# oscillVRL75.net
KiCad netlist of a schematic drawn in EAGLE
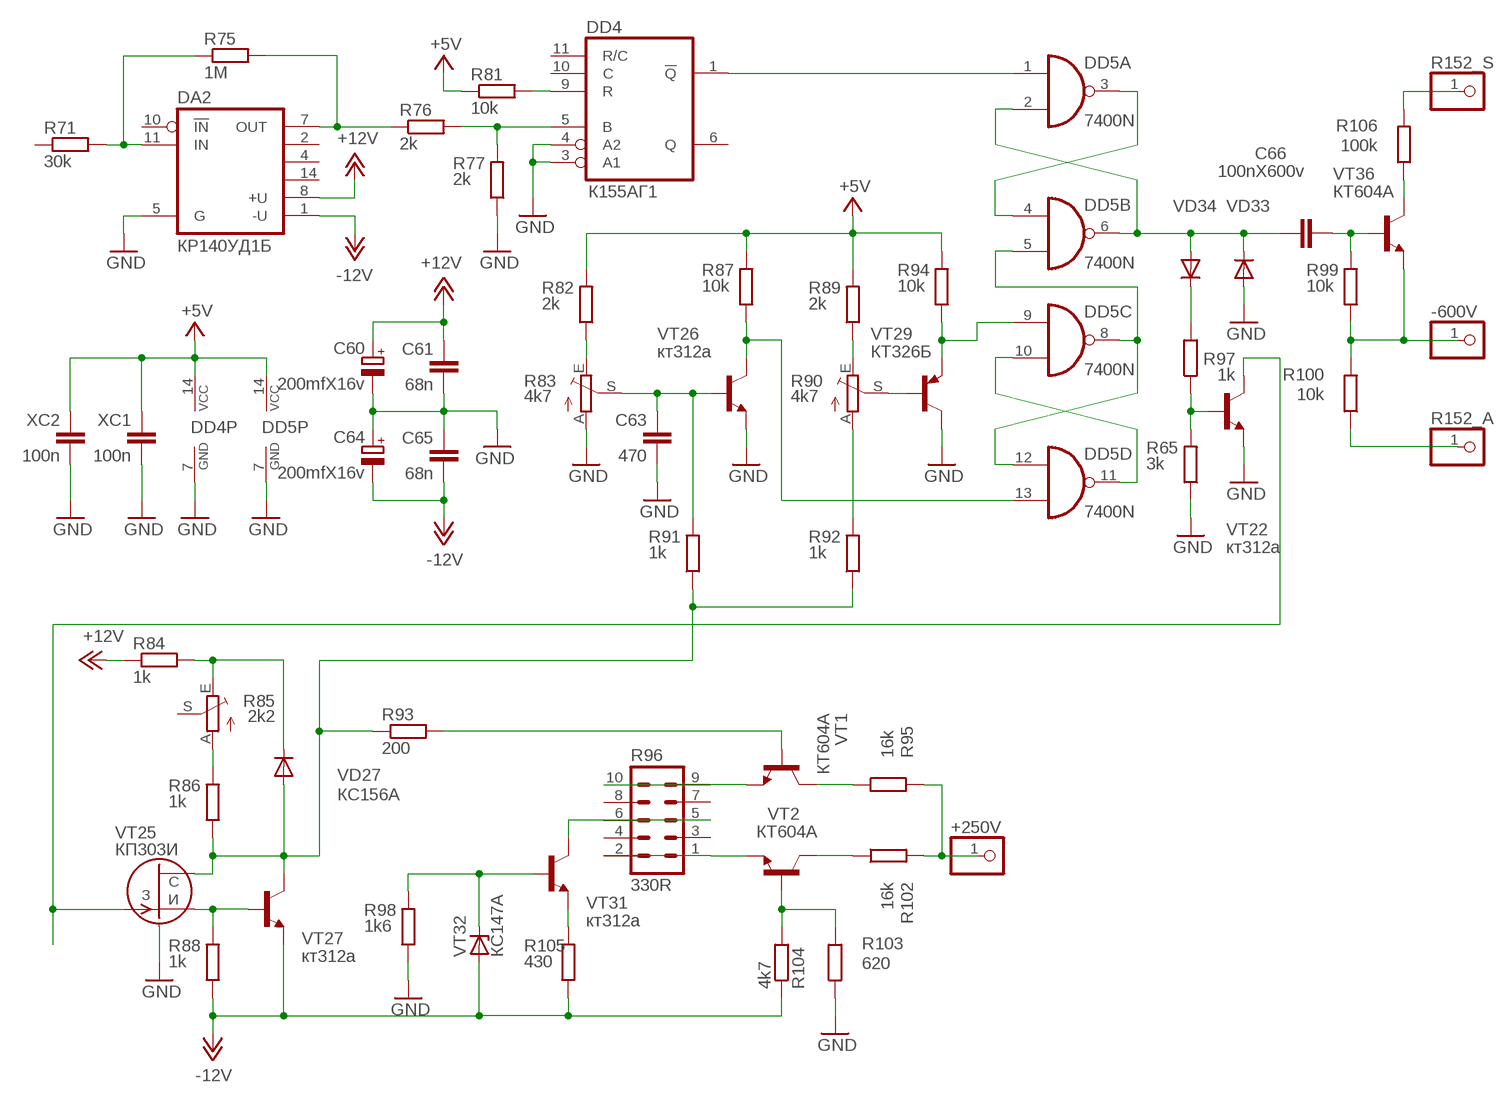
[diagram p0: schematic, sheet 1]

(export (version "E")
  (design (tool "Eeschema 10.0.6"))
  (components
    (comp (ref "+250V")
      (value "PINHD-1X1")
      (footprint "eagle-import:1X01")
      (libsource (lib "eagle-import") (part "PINHD-1X1"))
    )
    (comp (ref "-600V")
      (value "PINHD-1X1")
      (footprint "eagle-import:1X01")
      (libsource (lib "eagle-import") (part "PINHD-1X1"))
    )
    (comp (ref "C60")
      (value "200mfX16v")
      (footprint "eagle-import:E2,5-6")
      (libsource (lib "eagle-import") (part "CPOL-EUE2.5-6"))
    )
    (comp (ref "C61")
      (value "68n")
      (footprint "eagle-import:C0805")
      (libsource (lib "eagle-import") (part "C-EUC0805"))
    )
    (comp (ref "C63")
      (value "470")
      (footprint "eagle-import:C025-025X050")
      (libsource (lib "eagle-import") (part "C-EU025-025X050"))
    )
    (comp (ref "C64")
      (value "200mfX16v")
      (footprint "eagle-import:E2,5-6")
      (libsource (lib "eagle-import") (part "CPOL-EUE2.5-6"))
    )
    (comp (ref "C65")
      (value "68n")
      (footprint "eagle-import:C0805")
      (libsource (lib "eagle-import") (part "C-EUC0805"))
    )
    (comp (ref "C66")
      (value "100nX600v")
      (footprint "eagle-import:C050-025X075")
      (libsource (lib "eagle-import") (part "C-EU050-025X075"))
    )
    (comp (ref "DA2")
      (value "КР140УД1Б")
      (footprint "eagle-import:DIL14")
      (libsource (lib "eagle-import") (part "140UD1(KR)"))
    )
    (comp (ref "DD4")
      (value "К155АГ1")
      (footprint "eagle-import:DIL14")
      (libsource (lib "eagle-import") (part "74121N"))
    )
    (comp (ref "DD5")
      (value "7400N")
      (footprint "eagle-import:DIL14")
      (libsource (lib "eagle-import") (part "7400N"))
    )
    (comp (ref "R65")
      (value "3k")
      (footprint "eagle-import:M0805")
      (libsource (lib "eagle-import") (part "R-EU_M0805"))
    )
    (comp (ref "R71")
      (value "30k")
      (footprint "eagle-import:M0805")
      (libsource (lib "eagle-import") (part "R-EU_M0805"))
    )
    (comp (ref "R75")
      (value "1M")
      (footprint "eagle-import:M0805")
      (libsource (lib "eagle-import") (part "R-EU_M0805"))
    )
    (comp (ref "R76")
      (value "2k")
      (footprint "eagle-import:M0805")
      (libsource (lib "eagle-import") (part "R-EU_M0805"))
    )
    (comp (ref "R77")
      (value "2k")
      (footprint "eagle-import:M0805")
      (libsource (lib "eagle-import") (part "R-EU_M0805"))
    )
    (comp (ref "R81")
      (value "10k")
      (footprint "eagle-import:M0805")
      (libsource (lib "eagle-import") (part "R-EU_M0805"))
    )
    (comp (ref "R82")
      (value "2k")
      (footprint "eagle-import:M0805")
      (libsource (lib "eagle-import") (part "R-EU_M0805"))
    )
    (comp (ref "R83")
      (value "4k7")
      (footprint "eagle-import:S64Y")
      (libsource (lib "eagle-import") (part "TRIM_EU-S64Y"))
    )
    (comp (ref "R84")
      (value "1k")
      (footprint "eagle-import:M0805")
      (libsource (lib "eagle-import") (part "R-EU_M0805"))
    )
    (comp (ref "R85")
      (value "2k2")
      (footprint "eagle-import:S64Y")
      (libsource (lib "eagle-import") (part "TRIM_EU-S64Y"))
    )
    (comp (ref "R86")
      (value "1k")
      (footprint "eagle-import:M0805")
      (libsource (lib "eagle-import") (part "R-EU_M0805"))
    )
    (comp (ref "R87")
      (value "10k")
      (footprint "eagle-import:M0805")
      (libsource (lib "eagle-import") (part "R-EU_M0805"))
    )
    (comp (ref "R88")
      (value "1k")
      (footprint "eagle-import:M0805")
      (libsource (lib "eagle-import") (part "R-EU_M0805"))
    )
    (comp (ref "R89")
      (value "2k")
      (footprint "eagle-import:M0805")
      (libsource (lib "eagle-import") (part "R-EU_M0805"))
    )
    (comp (ref "R90")
      (value "4k7")
      (footprint "eagle-import:S64Y")
      (libsource (lib "eagle-import") (part "TRIM_EU-S64Y"))
    )
    (comp (ref "R91")
      (value "1k")
      (footprint "eagle-import:M0805")
      (libsource (lib "eagle-import") (part "R-EU_M0805"))
    )
    (comp (ref "R92")
      (value "1k")
      (footprint "eagle-import:M0805")
      (libsource (lib "eagle-import") (part "R-EU_M0805"))
    )
    (comp (ref "R93")
      (value "200")
      (footprint "eagle-import:M0805")
      (libsource (lib "eagle-import") (part "R-EU_M0805"))
    )
    (comp (ref "R94")
      (value "10k")
      (footprint "eagle-import:M0805")
      (libsource (lib "eagle-import") (part "R-EU_M0805"))
    )
    (comp (ref "R95")
      (value "16k")
      (footprint "eagle-import:M1206")
      (libsource (lib "eagle-import") (part "R-EU_M1206"))
    )
    (comp (ref "R96")
      (value "330R")
      (footprint "eagle-import:MA05-2")
      (libsource (lib "eagle-import") (part "MA05-2"))
    )
    (comp (ref "R97")
      (value "1k")
      (footprint "eagle-import:M0805")
      (libsource (lib "eagle-import") (part "R-EU_M0805"))
    )
    (comp (ref "R98")
      (value "1k6")
      (footprint "eagle-import:M0805")
      (libsource (lib "eagle-import") (part "R-EU_M0805"))
    )
    (comp (ref "R99")
      (value "10k")
      (footprint "eagle-import:M1206")
      (libsource (lib "eagle-import") (part "R-EU_M1206"))
    )
    (comp (ref "R100")
      (value "10k")
      (footprint "eagle-import:M1206")
      (libsource (lib "eagle-import") (part "R-EU_M1206"))
    )
    (comp (ref "R102")
      (value "16k")
      (footprint "eagle-import:M1206")
      (libsource (lib "eagle-import") (part "R-EU_M1206"))
    )
    (comp (ref "R103")
      (value "620")
      (footprint "eagle-import:M1206")
      (libsource (lib "eagle-import") (part "R-EU_M1206"))
    )
    (comp (ref "R104")
      (value "4k7")
      (footprint "eagle-import:M1206")
      (libsource (lib "eagle-import") (part "R-EU_M1206"))
    )
    (comp (ref "R105")
      (value "430")
      (footprint "eagle-import:M0805")
      (libsource (lib "eagle-import") (part "R-EU_M0805"))
    )
    (comp (ref "R106")
      (value "100k")
      (footprint "eagle-import:M1206")
      (libsource (lib "eagle-import") (part "R-EU_M1206"))
    )
    (comp (ref "R152_A")
      (value "PINHD-1X1")
      (footprint "eagle-import:1X01")
      (libsource (lib "eagle-import") (part "PINHD-1X1"))
    )
    (comp (ref "R152_S")
      (value "PINHD-1X1")
      (footprint "eagle-import:1X01")
      (libsource (lib "eagle-import") (part "PINHD-1X1"))
    )
    (comp (ref "VD27")
      (value "КС156А")
      (footprint "eagle-import:SOD80C")
      (libsource (lib "eagle-import") (part "DIODE-SOD80C"))
    )
    (comp (ref "VD33")
      (value "DIODE-SOD80C")
      (footprint "eagle-import:SOD80C")
      (libsource (lib "eagle-import") (part "DIODE-SOD80C"))
    )
    (comp (ref "VD34")
      (value "DIODE-SOD80C")
      (footprint "eagle-import:SOD80C")
      (libsource (lib "eagle-import") (part "DIODE-SOD80C"))
    )
    (comp (ref "VT1")
      (value "КТ604А")
      (footprint "eagle-import:TO126V")
      (libsource (lib "eagle-import") (part "-NPN-TO126V"))
    )
    (comp (ref "VT2")
      (value "КТ604А")
      (footprint "eagle-import:TO126V")
      (libsource (lib "eagle-import") (part "-NPN-TO126V"))
    )
    (comp (ref "VT22")
      (value "кт312а")
      (footprint "eagle-import:TO92-ECB")
      (libsource (lib "eagle-import") (part "-NPN-TO92-ECB"))
    )
    (comp (ref "VT25")
      (value "КП303И")
      (footprint "eagle-import:TO72")
      (libsource (lib "eagle-import") (part "КП303И"))
    )
    (comp (ref "VT26")
      (value "кт312а")
      (footprint "eagle-import:TO92-ECB")
      (libsource (lib "eagle-import") (part "-NPN-TO92-ECB"))
    )
    (comp (ref "VT27")
      (value "кт312а")
      (footprint "eagle-import:TO92-ECB")
      (libsource (lib "eagle-import") (part "-NPN-TO92-ECB"))
    )
    (comp (ref "VT29")
      (value "КТ326Б")
      (footprint "eagle-import:TO18")
      (libsource (lib "eagle-import") (part "-PNP-TO18-EBC2N3963"))
    )
    (comp (ref "VT31")
      (value "кт312а")
      (footprint "eagle-import:TO92-ECB")
      (libsource (lib "eagle-import") (part "-NPN-TO92-ECB"))
    )
    (comp (ref "VT32")
      (value "КС147А")
      (footprint "eagle-import:DO35Z10")
      (libsource (lib "eagle-import") (part "ZENER-DIODEDO35Z10"))
    )
    (comp (ref "VT36")
      (value "КТ604А")
      (footprint "eagle-import:TO126V")
      (libsource (lib "eagle-import") (part "-NPN-TO126V"))
    )
    (comp (ref "XC1")
      (value "100n")
      (footprint "eagle-import:C0805")
      (libsource (lib "eagle-import") (part "C-EUC0805"))
    )
    (comp (ref "XC2")
      (value "100n")
      (footprint "eagle-import:C0805")
      (libsource (lib "eagle-import") (part "C-EUC0805"))
    )
  )
  (nets
    (net (code "1") (name "+5V") (class "Default")
      (node (ref "DD4") (pin "14") (pinfunction "VCC_14") (pintype "power_in"))
      (node (ref "DD5") (pin "14") (pinfunction "VCC_14") (pintype "power_in"))
      (node (ref "R81") (pin "1") (pinfunction "1_1") (pintype "passive"))
      (node (ref "R82") (pin "2") (pinfunction "2_2") (pintype "passive"))
      (node (ref "R87") (pin "2") (pinfunction "2_2") (pintype "passive"))
      (node (ref "R89") (pin "2") (pinfunction "2_2") (pintype "passive"))
      (node (ref "R94") (pin "2") (pinfunction "2_2") (pintype "passive"))
      (node (ref "XC1") (pin "1") (pinfunction "1_1") (pintype "passive"))
      (node (ref "XC2") (pin "1") (pinfunction "1_1") (pintype "passive"))
    )
    (net (code "2") (name "+12V") (class "Default")
      (node (ref "C60") (pin "+") (pinfunction "+_+") (pintype "passive"))
      (node (ref "C61") (pin "1") (pinfunction "1_1") (pintype "passive"))
      (node (ref "DA2") (pin "8") (pinfunction "+U_8") (pintype "input"))
      (node (ref "R84") (pin "1") (pinfunction "1_1") (pintype "passive"))
    )
    (net (code "3") (name "-12V") (class "Default")
      (node (ref "C64") (pin "-") (pinfunction "-_-") (pintype "passive"))
      (node (ref "C65") (pin "2") (pinfunction "2_2") (pintype "passive"))
      (node (ref "DA2") (pin "1") (pinfunction "-U_1") (pintype "input"))
      (node (ref "R104") (pin "1") (pinfunction "1_1") (pintype "passive"))
      (node (ref "R105") (pin "1") (pinfunction "1_1") (pintype "passive"))
      (node (ref "R88") (pin "1") (pinfunction "1_1") (pintype "passive"))
      (node (ref "VT27") (pin "E") (pinfunction "E_E") (pintype "passive"))
      (node (ref "VT32") (pin "A") (pinfunction "A_A") (pintype "passive"))
    )
    (net (code "4") (name "GND") (class "Default")
      (node (ref "C60") (pin "-") (pinfunction "-_-") (pintype "passive"))
      (node (ref "C61") (pin "2") (pinfunction "2_2") (pintype "passive"))
      (node (ref "C63") (pin "2") (pinfunction "2_2") (pintype "passive"))
      (node (ref "C64") (pin "+") (pinfunction "+_+") (pintype "passive"))
      (node (ref "C65") (pin "1") (pinfunction "1_1") (pintype "passive"))
      (node (ref "DA2") (pin "5") (pinfunction "G_5") (pintype "input"))
      (node (ref "DD4") (pin "3") (pinfunction "A1_3") (pintype "input"))
      (node (ref "DD4") (pin "4") (pinfunction "A2_4") (pintype "input"))
      (node (ref "DD4") (pin "7") (pinfunction "GND_7") (pintype "power_in"))
      (node (ref "DD5") (pin "7") (pinfunction "GND_7") (pintype "power_in"))
      (node (ref "R103") (pin "1") (pinfunction "1_1") (pintype "passive"))
      (node (ref "R65") (pin "1") (pinfunction "1_1") (pintype "passive"))
      (node (ref "R77") (pin "1") (pinfunction "1_1") (pintype "passive"))
      (node (ref "R83") (pin "A") (pinfunction "A_A") (pintype "passive"))
      (node (ref "R98") (pin "1") (pinfunction "1_1") (pintype "passive"))
      (node (ref "VD33") (pin "A") (pinfunction "A_A") (pintype "passive"))
      (node (ref "VT22") (pin "E") (pinfunction "E_E") (pintype "passive"))
      (node (ref "VT25") (pin "4") (pinfunction "GND_4") (pintype "bidirectional"))
      (node (ref "VT26") (pin "E") (pinfunction "E_E") (pintype "passive"))
      (node (ref "VT29") (pin "3") (pinfunction "C_3") (pintype "passive"))
      (node (ref "XC1") (pin "2") (pinfunction "2_2") (pintype "passive"))
      (node (ref "XC2") (pin "2") (pinfunction "2_2") (pintype "passive"))
    )
    (net (code "5") (name "Net-(+250V-Pad1)") (class "Default")
      (node (ref "+250V") (pin "1") (pinfunction "1_1") (pintype "passive"))
      (node (ref "R102") (pin "2") (pinfunction "2_2") (pintype "passive"))
      (node (ref "R95") (pin "2") (pinfunction "2_2") (pintype "passive"))
    )
    (net (code "6") (name "Net-(C63-Pad1)") (class "Default")
      (node (ref "C63") (pin "1") (pinfunction "1_1") (pintype "passive"))
      (node (ref "R83") (pin "S") (pinfunction "S_S") (pintype "passive"))
      (node (ref "R91") (pin "2") (pinfunction "2_2") (pintype "passive"))
      (node (ref "VT26") (pin "B") (pinfunction "B_B") (pintype "passive"))
    )
    (net (code "7") (name "Net-(DA2-IN)") (class "Default")
      (node (ref "DA2") (pin "11") (pinfunction "IN_11") (pintype "input"))
      (node (ref "R71") (pin "2") (pinfunction "2_2") (pintype "passive"))
      (node (ref "R75") (pin "1") (pinfunction "1_1") (pintype "passive"))
    )
    (net (code "8") (name "Net-(DA2-OUT)") (class "Default")
      (node (ref "DA2") (pin "7") (pinfunction "OUT_7") (pintype "input"))
      (node (ref "R75") (pin "2") (pinfunction "2_2") (pintype "passive"))
      (node (ref "R76") (pin "1") (pinfunction "1_1") (pintype "passive"))
    )
    (net (code "9") (name "Net-(DD4A-B)") (class "Default")
      (node (ref "DD4") (pin "5") (pinfunction "B_5") (pintype "input"))
      (node (ref "R76") (pin "2") (pinfunction "2_2") (pintype "passive"))
      (node (ref "R77") (pin "2") (pinfunction "2_2") (pintype "passive"))
    )
    (net (code "10") (name "Net-(DD4A-R)") (class "Default")
      (node (ref "DD4") (pin "9") (pinfunction "R_9") (pintype "input"))
      (node (ref "R81") (pin "2") (pinfunction "2_2") (pintype "passive"))
    )
    (net (code "11") (name "Net-(DD4A-~{Q})") (class "Default")
      (node (ref "DD4") (pin "1") (pinfunction "~{Q}_1") (pintype "output"))
      (node (ref "DD5") (pin "1") (pinfunction "I0_1") (pintype "input"))
    )
    (net (code "12") (name "Net-(DD5A-I1)") (class "Default")
      (node (ref "C66") (pin "1") (pinfunction "1_1") (pintype "passive"))
      (node (ref "DD5") (pin "2") (pinfunction "I1_2") (pintype "input"))
      (node (ref "DD5") (pin "6") (pinfunction "O_6") (pintype "output"))
      (node (ref "VD33") (pin "C") (pinfunction "C_C") (pintype "passive"))
      (node (ref "VD34") (pin "A") (pinfunction "A_A") (pintype "passive"))
    )
    (net (code "13") (name "Net-(DD5A-O)") (class "Default")
      (node (ref "DD5") (pin "3") (pinfunction "O_3") (pintype "output"))
      (node (ref "DD5") (pin "4") (pinfunction "I0_4") (pintype "input"))
    )
    (net (code "14") (name "Net-(DD5B-I1)") (class "Default")
      (node (ref "DD5") (pin "12") (pinfunction "I0_12") (pintype "input"))
      (node (ref "DD5") (pin "5") (pinfunction "I1_5") (pintype "input"))
      (node (ref "DD5") (pin "8") (pinfunction "O_8") (pintype "output"))
    )
    (net (code "15") (name "Net-(DD5C-I0)") (class "Default")
      (node (ref "DD5") (pin "9") (pinfunction "I0_9") (pintype "input"))
      (node (ref "R94") (pin "1") (pinfunction "1_1") (pintype "passive"))
      (node (ref "VT29") (pin "1") (pinfunction "E_1") (pintype "passive"))
    )
    (net (code "16") (name "Net-(DD5C-I1)") (class "Default")
      (node (ref "DD5") (pin "10") (pinfunction "I1_10") (pintype "input"))
      (node (ref "DD5") (pin "11") (pinfunction "O_11") (pintype "output"))
    )
    (net (code "17") (name "Net-(DD5D-I1)") (class "Default")
      (node (ref "DD5") (pin "13") (pinfunction "I1_13") (pintype "input"))
      (node (ref "R87") (pin "1") (pinfunction "1_1") (pintype "passive"))
      (node (ref "VT26") (pin "C") (pinfunction "C_C") (pintype "passive"))
    )
    (net (code "18") (name "Net-(R65-Pad2)") (class "Default")
      (node (ref "R65") (pin "2") (pinfunction "2_2") (pintype "passive"))
      (node (ref "R97") (pin "1") (pinfunction "1_1") (pintype "passive"))
      (node (ref "VT22") (pin "B") (pinfunction "B_B") (pintype "passive"))
    )
    (net (code "19") (name "Net-(R82-Pad1)") (class "Default")
      (node (ref "R82") (pin "1") (pinfunction "1_1") (pintype "passive"))
      (node (ref "R83") (pin "E") (pinfunction "E_E") (pintype "passive"))
    )
    (net (code "20") (name "Net-(R84-Pad2)") (class "Default")
      (node (ref "R84") (pin "2") (pinfunction "2_2") (pintype "passive"))
      (node (ref "R85") (pin "E") (pinfunction "E_E") (pintype "passive"))
      (node (ref "VD27") (pin "C") (pinfunction "C_C") (pintype "passive"))
    )
    (net (code "21") (name "Net-(R85-PadA)") (class "Default")
      (node (ref "R85") (pin "A") (pinfunction "A_A") (pintype "passive"))
      (node (ref "R86") (pin "2") (pinfunction "2_2") (pintype "passive"))
    )
    (net (code "22") (name "Net-(R89-Pad1)") (class "Default")
      (node (ref "R89") (pin "1") (pinfunction "1_1") (pintype "passive"))
      (node (ref "R90") (pin "E") (pinfunction "E_E") (pintype "passive"))
    )
    (net (code "23") (name "Net-(R90-PadA)") (class "Default")
      (node (ref "R90") (pin "A") (pinfunction "A_A") (pintype "passive"))
      (node (ref "R92") (pin "2") (pinfunction "2_2") (pintype "passive"))
    )
    (net (code "24") (name "Net-(R96-Pad5)") (class "Default")
      (node (ref "R96") (pin "5") (pinfunction "5_5") (pintype "passive"))
      (node (ref "R96") (pin "6") (pinfunction "6_6") (pintype "passive"))
      (node (ref "VT31") (pin "C") (pinfunction "C_C") (pintype "passive"))
    )
    (net (code "25") (name "Net-(R97-Pad2)") (class "Default")
      (node (ref "R97") (pin "2") (pinfunction "2_2") (pintype "passive"))
      (node (ref "VD34") (pin "C") (pinfunction "C_C") (pintype "passive"))
    )
    (net (code "26") (name "Net-(R98-Pad2)") (class "Default")
      (node (ref "R98") (pin "2") (pinfunction "2_2") (pintype "passive"))
      (node (ref "VT31") (pin "B") (pinfunction "B_B") (pintype "passive"))
      (node (ref "VT32") (pin "C") (pinfunction "C_C") (pintype "passive"))
    )
    (net (code "27") (name "Net-(R100-Pad1)") (class "Default")
      (node (ref "R100") (pin "1") (pinfunction "1_1") (pintype "passive"))
      (node (ref "R152_A") (pin "1") (pinfunction "1_1") (pintype "passive"))
    )
    (net (code "28") (name "Net-(R105-Pad2)") (class "Default")
      (node (ref "R105") (pin "2") (pinfunction "2_2") (pintype "passive"))
      (node (ref "VT31") (pin "E") (pinfunction "E_E") (pintype "passive"))
    )
    (net (code "29") (name "Net-(R106-Pad2)") (class "Default")
      (node (ref "R106") (pin "2") (pinfunction "2_2") (pintype "passive"))
      (node (ref "R152_S") (pin "1") (pinfunction "1_1") (pintype "passive"))
    )
    (net (code "30") (name "Net-(VT1-B)") (class "Default")
      (node (ref "R93") (pin "2") (pinfunction "2_2") (pintype "passive"))
      (node (ref "VT1") (pin "3") (pinfunction "B_3") (pintype "passive"))
    )
    (net (code "31") (name "Net-(VT1-C)") (class "Default")
      (node (ref "R95") (pin "1") (pinfunction "1_1") (pintype "passive"))
      (node (ref "VT1") (pin "2") (pinfunction "C_2") (pintype "passive"))
    )
    (net (code "32") (name "Net-(VT1-E)") (class "Default")
      (node (ref "R96") (pin "10") (pinfunction "10_10") (pintype "passive"))
      (node (ref "R96") (pin "9") (pinfunction "9_9") (pintype "passive"))
      (node (ref "VT1") (pin "1") (pinfunction "E_1") (pintype "passive"))
    )
    (net (code "33") (name "Net-(VT2-B)") (class "Default")
      (node (ref "R103") (pin "2") (pinfunction "2_2") (pintype "passive"))
      (node (ref "R104") (pin "2") (pinfunction "2_2") (pintype "passive"))
      (node (ref "VT2") (pin "3") (pinfunction "B_3") (pintype "passive"))
    )
    (net (code "34") (name "Net-(VT2-C)") (class "Default")
      (node (ref "R102") (pin "1") (pinfunction "1_1") (pintype "passive"))
      (node (ref "VT2") (pin "2") (pinfunction "C_2") (pintype "passive"))
    )
    (net (code "35") (name "Net-(VT2-E)") (class "Default")
      (node (ref "R96") (pin "1") (pinfunction "1_1") (pintype "passive"))
      (node (ref "R96") (pin "2") (pinfunction "2_2") (pintype "passive"))
      (node (ref "VT2") (pin "1") (pinfunction "E_1") (pintype "passive"))
    )
    (net (code "36") (name "Net-(VT25-D)") (class "Default")
      (node (ref "R86") (pin "1") (pinfunction "1_1") (pintype "passive"))
      (node (ref "R91") (pin "1") (pinfunction "1_1") (pintype "passive"))
      (node (ref "R92") (pin "1") (pinfunction "1_1") (pintype "passive"))
      (node (ref "R93") (pin "1") (pinfunction "1_1") (pintype "passive"))
      (node (ref "VD27") (pin "A") (pinfunction "A_A") (pintype "passive"))
      (node (ref "VT25") (pin "2") (pinfunction "D_2") (pintype "passive"))
      (node (ref "VT27") (pin "C") (pinfunction "C_C") (pintype "passive"))
    )
    (net (code "37") (name "Net-(VT25-G)") (class "Default")
      (node (ref "VT22") (pin "C") (pinfunction "C_C") (pintype "passive"))
      (node (ref "VT25") (pin "3") (pinfunction "G_3") (pintype "passive"))
    )
    (net (code "38") (name "Net-(VT25-S)") (class "Default")
      (node (ref "R88") (pin "2") (pinfunction "2_2") (pintype "passive"))
      (node (ref "VT25") (pin "1") (pinfunction "S_1") (pintype "passive"))
      (node (ref "VT27") (pin "B") (pinfunction "B_B") (pintype "passive"))
    )
    (net (code "39") (name "Net-(VT29-B)") (class "Default")
      (node (ref "R90") (pin "S") (pinfunction "S_S") (pintype "passive"))
      (node (ref "VT29") (pin "2") (pinfunction "B_2") (pintype "passive"))
    )
    (net (code "40") (name "Net-(VT36-B)") (class "Default")
      (node (ref "C66") (pin "2") (pinfunction "2_2") (pintype "passive"))
      (node (ref "R99") (pin "2") (pinfunction "2_2") (pintype "passive"))
      (node (ref "VT36") (pin "3") (pinfunction "B_3") (pintype "passive"))
    )
    (net (code "41") (name "Net-(VT36-C)") (class "Default")
      (node (ref "R106") (pin "1") (pinfunction "1_1") (pintype "passive"))
      (node (ref "VT36") (pin "2") (pinfunction "C_2") (pintype "passive"))
    )
    (net (code "42") (name "Net-(VT36-E)") (class "Default")
      (node (ref "-600V") (pin "1") (pinfunction "1_1") (pintype "passive"))
      (node (ref "R100") (pin "2") (pinfunction "2_2") (pintype "passive"))
      (node (ref "R99") (pin "1") (pinfunction "1_1") (pintype "passive"))
      (node (ref "VT36") (pin "1") (pinfunction "E_1") (pintype "passive"))
    )
    (net (code "43") (name "unconnected-(DA2-3-Pad4)") (class "Default")
      (node (ref "DA2") (pin "4") (pinfunction "3_4") (pintype "input"))
    )
    (net (code "44") (name "unconnected-(DA2-12-Pad14)") (class "Default")
      (node (ref "DA2") (pin "14") (pinfunction "12_14") (pintype "input"))
    )
    (net (code "45") (name "unconnected-(DA2-Pad2)") (class "Default")
      (node (ref "DA2") (pin "2") (pinfunction "2_2") (pintype "input"))
    )
    (net (code "46") (name "unconnected-(DA2-~{IN}-Pad10)") (class "Default")
      (node (ref "DA2") (pin "10") (pinfunction "~{IN}_10") (pintype "input"))
    )
    (net (code "47") (name "unconnected-(DD4A-C-Pad10)") (class "Default")
      (node (ref "DD4") (pin "10") (pinfunction "C_10") (pintype "input"))
    )
    (net (code "48") (name "unconnected-(DD4A-Q-Pad6)") (class "Default")
      (node (ref "DD4") (pin "6") (pinfunction "Q_6") (pintype "output"))
    )
    (net (code "49") (name "unconnected-(DD4A-R{slash}C-Pad11)") (class "Default")
      (node (ref "DD4") (pin "11") (pinfunction "R/C_11") (pintype "input"))
    )
    (net (code "50") (name "unconnected-(R71-Pad1)") (class "Default")
      (node (ref "R71") (pin "1") (pinfunction "1_1") (pintype "passive"))
    )
    (net (code "51") (name "unconnected-(R85-PadS)") (class "Default")
      (node (ref "R85") (pin "S") (pinfunction "S_S") (pintype "passive"))
    )
    (net (code "52") (name "unconnected-(R96-Pad3)") (class "Default")
      (node (ref "R96") (pin "3") (pinfunction "3_3") (pintype "passive"))
    )
    (net (code "53") (name "unconnected-(R96-Pad4)") (class "Default")
      (node (ref "R96") (pin "4") (pinfunction "4_4") (pintype "passive"))
    )
    (net (code "54") (name "unconnected-(R96-Pad7)") (class "Default")
      (node (ref "R96") (pin "7") (pinfunction "7_7") (pintype "passive"))
    )
    (net (code "55") (name "unconnected-(R96-Pad8)") (class "Default")
      (node (ref "R96") (pin "8") (pinfunction "8_8") (pintype "passive"))
    )
  )
)
